# DCF-amplifier.net
KiCad netlist of a schematic drawn in EAGLE
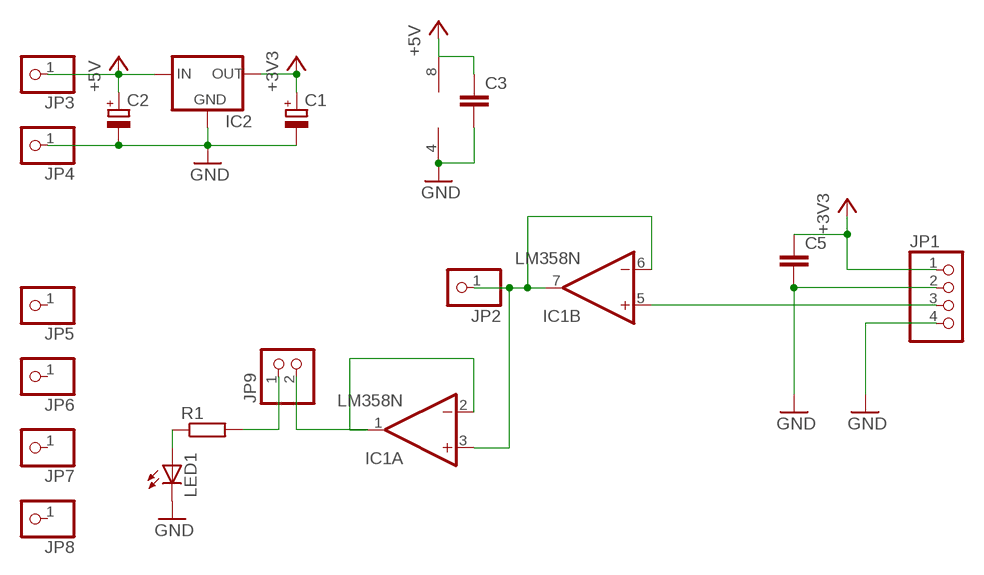
[diagram p0: schematic, sheet 1]

(export (version "E")
  (design (tool "Eeschema 10.0.6"))
  (components
    (comp (ref "C1")
      (value "CPOL-EUE2.5-5")
      (footprint "eagle-import:E2,5-5")
      (libsource (lib "eagle-import") (part "CPOL-EUE2.5-5"))
    )
    (comp (ref "C2")
      (value "CPOL-EUE2.5-5")
      (footprint "eagle-import:E2,5-5")
      (libsource (lib "eagle-import") (part "CPOL-EUE2.5-5"))
    )
    (comp (ref "C3")
      (value "C-EU025-025X050")
      (footprint "eagle-import:C025-025X050")
      (libsource (lib "eagle-import") (part "C-EU025-025X050"))
    )
    (comp (ref "C5")
      (value "C-EU025-025X050")
      (footprint "eagle-import:C025-025X050")
      (libsource (lib "eagle-import") (part "C-EU025-025X050"))
    )
    (comp (ref "IC1")
      (value "LM358N")
      (footprint "eagle-import:DIL08")
      (libsource (lib "eagle-import") (part "LM358N"))
    )
    (comp (ref "IC2")
      (value "78XXL")
      (footprint "eagle-import:78XXL")
      (libsource (lib "eagle-import") (part "78XXL"))
    )
    (comp (ref "JP1")
      (value "PINHD-1X4")
      (footprint "eagle-import:1X04")
      (libsource (lib "eagle-import") (part "PINHD-1X4"))
    )
    (comp (ref "JP2")
      (value "PINHD-1X1")
      (footprint "eagle-import:1X01")
      (libsource (lib "eagle-import") (part "PINHD-1X1"))
    )
    (comp (ref "JP3")
      (value "PINHD-1X1")
      (footprint "eagle-import:1X01")
      (libsource (lib "eagle-import") (part "PINHD-1X1"))
    )
    (comp (ref "JP4")
      (value "PINHD-1X1")
      (footprint "eagle-import:1X01")
      (libsource (lib "eagle-import") (part "PINHD-1X1"))
    )
    (comp (ref "JP5")
      (value "PINHD-1X1")
      (footprint "eagle-import:1X01")
      (libsource (lib "eagle-import") (part "PINHD-1X1"))
    )
    (comp (ref "JP6")
      (value "PINHD-1X1")
      (footprint "eagle-import:1X01")
      (libsource (lib "eagle-import") (part "PINHD-1X1"))
    )
    (comp (ref "JP7")
      (value "PINHD-1X1")
      (footprint "eagle-import:1X01")
      (libsource (lib "eagle-import") (part "PINHD-1X1"))
    )
    (comp (ref "JP8")
      (value "PINHD-1X1")
      (footprint "eagle-import:1X01")
      (libsource (lib "eagle-import") (part "PINHD-1X1"))
    )
    (comp (ref "JP9")
      (value "PINHD-1X2")
      (footprint "eagle-import:1X02")
      (libsource (lib "eagle-import") (part "PINHD-1X2"))
    )
    (comp (ref "LED1")
      (value "LED5MM")
      (footprint "eagle-import:LED5MM")
      (libsource (lib "eagle-import") (part "LED5MM"))
    )
    (comp (ref "R1")
      (value "R-EU_0309/10")
      (footprint "eagle-import:0309_10")
      (libsource (lib "eagle-import") (part "R-EU_0309/10"))
    )
  )
  (nets
    (net (code "1") (name "+3V3") (class "Default")
      (node (ref "C1") (pin "+") (pinfunction "+_+") (pintype "passive"))
      (node (ref "C5") (pin "1") (pinfunction "1_1") (pintype "passive"))
      (node (ref "IC2") (pin "OUT") (pinfunction "OUT_OUT") (pintype "passive"))
      (node (ref "JP1") (pin "1") (pinfunction "1_1") (pintype "passive"))
    )
    (net (code "2") (name "+5V") (class "Default")
      (node (ref "C2") (pin "+") (pinfunction "+_+") (pintype "passive"))
      (node (ref "C3") (pin "1") (pinfunction "1_1") (pintype "passive"))
      (node (ref "IC1") (pin "8") (pinfunction "V+_8") (pintype "power_in"))
      (node (ref "IC2") (pin "IN") (pinfunction "IN_IN") (pintype "input"))
      (node (ref "JP3") (pin "1") (pinfunction "1_1") (pintype "passive"))
    )
    (net (code "3") (name "GND") (class "Default")
      (node (ref "C1") (pin "-") (pinfunction "-_-") (pintype "passive"))
      (node (ref "C2") (pin "-") (pinfunction "-_-") (pintype "passive"))
      (node (ref "C3") (pin "2") (pinfunction "2_2") (pintype "passive"))
      (node (ref "C5") (pin "2") (pinfunction "2_2") (pintype "passive"))
      (node (ref "IC1") (pin "4") (pinfunction "V-_4") (pintype "power_in"))
      (node (ref "IC2") (pin "GND") (pinfunction "GND_GND") (pintype "input"))
      (node (ref "JP1") (pin "2") (pinfunction "2_2") (pintype "passive"))
      (node (ref "JP1") (pin "4") (pinfunction "4_4") (pintype "passive"))
      (node (ref "JP4") (pin "1") (pinfunction "1_1") (pintype "passive"))
      (node (ref "LED1") (pin "K") (pinfunction "C_K") (pintype "passive"))
    )
    (net (code "4") (name "Net-(IC1A-+IN)") (class "Default")
      (node (ref "IC1") (pin "3") (pinfunction "+IN_3") (pintype "input"))
      (node (ref "IC1") (pin "6") (pinfunction "-IN_6") (pintype "input"))
      (node (ref "IC1") (pin "7") (pinfunction "OUT_7") (pintype "output"))
      (node (ref "JP2") (pin "1") (pinfunction "1_1") (pintype "passive"))
    )
    (net (code "5") (name "Net-(IC1A--IN)") (class "Default")
      (node (ref "IC1") (pin "1") (pinfunction "OUT_1") (pintype "output"))
      (node (ref "IC1") (pin "2") (pinfunction "-IN_2") (pintype "input"))
      (node (ref "JP9") (pin "2") (pinfunction "2_2") (pintype "passive"))
    )
    (net (code "6") (name "Net-(IC1B-+IN)") (class "Default")
      (node (ref "IC1") (pin "5") (pinfunction "+IN_5") (pintype "input"))
      (node (ref "JP1") (pin "3") (pinfunction "3_3") (pintype "passive"))
    )
    (net (code "7") (name "Net-(JP9-Pad1)") (class "Default")
      (node (ref "JP9") (pin "1") (pinfunction "1_1") (pintype "passive"))
      (node (ref "R1") (pin "2") (pinfunction "2_2") (pintype "passive"))
    )
    (net (code "8") (name "Net-(LED1-PadA)") (class "Default")
      (node (ref "LED1") (pin "A") (pinfunction "A_A") (pintype "passive"))
      (node (ref "R1") (pin "1") (pinfunction "1_1") (pintype "passive"))
    )
    (net (code "9") (name "unconnected-(JP5-Pad1)") (class "Default")
      (node (ref "JP5") (pin "1") (pinfunction "1_1") (pintype "passive"))
    )
    (net (code "10") (name "unconnected-(JP6-Pad1)") (class "Default")
      (node (ref "JP6") (pin "1") (pinfunction "1_1") (pintype "passive"))
    )
    (net (code "11") (name "unconnected-(JP7-Pad1)") (class "Default")
      (node (ref "JP7") (pin "1") (pinfunction "1_1") (pintype "passive"))
    )
    (net (code "12") (name "unconnected-(JP8-Pad1)") (class "Default")
      (node (ref "JP8") (pin "1") (pinfunction "1_1") (pintype "passive"))
    )
  )
)
